# 1_Power.net
KiCad netlist of a schematic drawn in Altium Designer
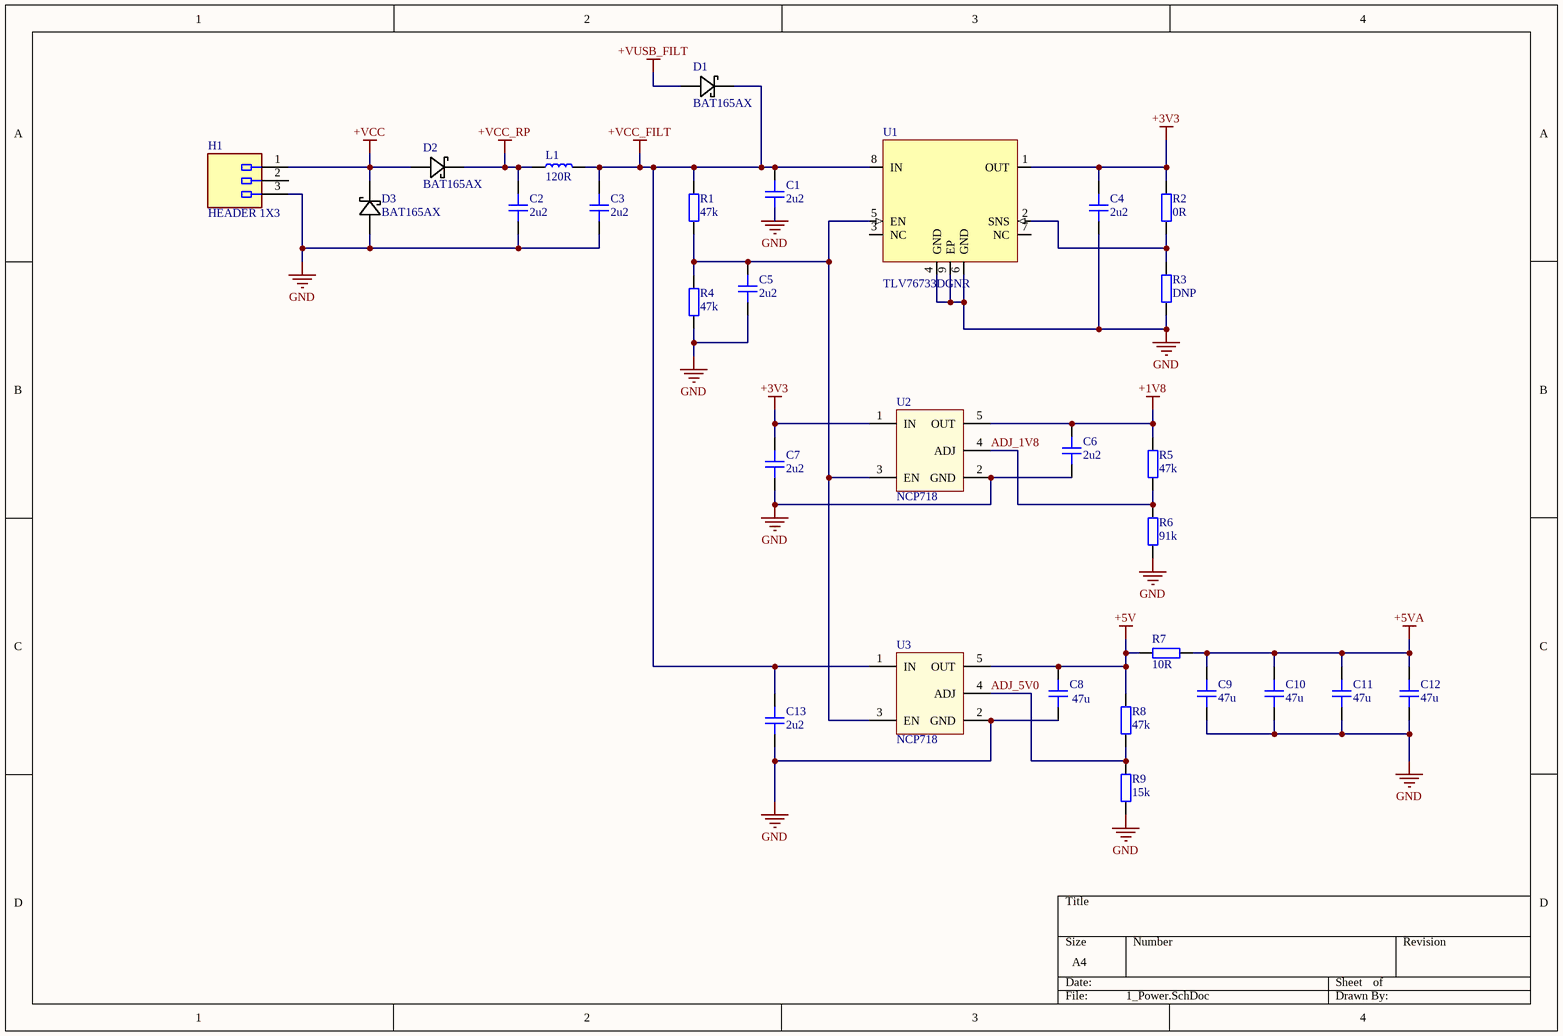
[diagram p0: 1_Power.SchDoc]

(export (version "E")
  (design (tool "Eeschema 10.0.6"))
  (components
    (comp (ref "C1")
      (value "2u2")
      (footprint "CAP_0201")
      (description "Capacitor SMD 0201")
      (libsource (lib "Schematic-Lib-PhilsLab") (part "CAP_0201"))
    )
    (comp (ref "C2")
      (value "2u2")
      (footprint "CAP_0201")
      (description "Capacitor SMD 0201")
      (libsource (lib "Schematic-Lib-PhilsLab") (part "CAP_0201"))
    )
    (comp (ref "C3")
      (value "2u2")
      (footprint "CAP_0201")
      (description "Capacitor SMD 0201")
      (libsource (lib "Schematic-Lib-PhilsLab") (part "CAP_0201"))
    )
    (comp (ref "C4")
      (value "2u2")
      (footprint "CAP_0201")
      (description "Capacitor SMD 0201")
      (libsource (lib "Schematic-Lib-PhilsLab") (part "CAP_0201"))
    )
    (comp (ref "C5")
      (value "2u2")
      (footprint "CAP_0201")
      (description "Capacitor SMD 0201")
      (libsource (lib "Schematic-Lib-PhilsLab") (part "CAP_0201"))
    )
    (comp (ref "C6")
      (value "2u2")
      (footprint "CAP_0201")
      (description "Capacitor SMD 0201")
      (libsource (lib "Schematic-Lib-PhilsLab") (part "CAP_0201"))
    )
    (comp (ref "C7")
      (value "2u2")
      (footprint "CAP_0201")
      (description "Capacitor SMD 0201")
      (libsource (lib "Schematic-Lib-PhilsLab") (part "CAP_0201"))
    )
    (comp (ref "C8")
      (value "47u")
      (footprint "CAP_0201")
      (description "Capacitor SMD 0201")
      (libsource (lib "Schematic-Lib-PhilsLab") (part "CAP_0201"))
    )
    (comp (ref "C9")
      (value "47u")
      (footprint "CAP_0201")
      (description "Capacitor SMD 0201")
      (libsource (lib "Schematic-Lib-PhilsLab") (part "CAP_0201"))
    )
    (comp (ref "C10")
      (value "47u")
      (footprint "CAP_0201")
      (description "Capacitor SMD 0201")
      (libsource (lib "Schematic-Lib-PhilsLab") (part "CAP_0201"))
    )
    (comp (ref "C11")
      (value "47u")
      (footprint "CAP_0201")
      (description "Capacitor SMD 0201")
      (libsource (lib "Schematic-Lib-PhilsLab") (part "CAP_0201"))
    )
    (comp (ref "C12")
      (value "47u")
      (footprint "CAP_0201")
      (description "Capacitor SMD 0201")
      (libsource (lib "Schematic-Lib-PhilsLab") (part "CAP_0201"))
    )
    (comp (ref "C13")
      (value "2u2")
      (footprint "CAP_0201")
      (description "Capacitor SMD 0201")
      (libsource (lib "Schematic-Lib-PhilsLab") (part "CAP_0201"))
    )
    (comp (ref "D1") (value "BAT165AX") (footprint "BAT165AX") (libsource (lib "SCHLib") (part "BAT165AX")))
    (comp (ref "D2") (value "BAT165AX") (footprint "BAT165AX") (libsource (lib "SCHLib") (part "BAT165AX")))
    (comp (ref "D3") (value "BAT165AX") (footprint "BAT165AX") (libsource (lib "SCHLib") (part "BAT165AX")))
    (comp (ref "H1")
      (value "HEADER 1X3")
      (footprint "053048-0310")
      (libsource (lib "SCHLib") (part "053048-0310"))
    )
    (comp (ref "L1")
      (value "120R")
      (footprint "IND_1008")
      (description "Inductor SMD 1008")
      (libsource (lib "Schematic-Lib-PhilsLab") (part "IND_1008"))
    )
    (comp (ref "R1")
      (value "47k")
      (footprint "RES_0402")
      (description "Resistor SMD 0402")
      (libsource (lib "Schematic-Lib-PhilsLab") (part "RES_0402"))
    )
    (comp (ref "R2")
      (value "0R")
      (footprint "RES_0805")
      (description "Resistor SMD 0805")
      (libsource (lib "Schematic-Lib-PhilsLab") (part "RES_0805"))
    )
    (comp (ref "R3")
      (value "DNP")
      (footprint "RES_0805")
      (description "Resistor SMD 0805")
      (libsource (lib "Schematic-Lib-PhilsLab") (part "RES_0805"))
    )
    (comp (ref "R4")
      (value "47k")
      (footprint "RES_0402")
      (description "Resistor SMD 0402")
      (libsource (lib "Schematic-Lib-PhilsLab") (part "RES_0402"))
    )
    (comp (ref "R5")
      (value "47k")
      (footprint "RES_0402")
      (description "Resistor SMD 0402")
      (libsource (lib "Schematic-Lib-PhilsLab") (part "RES_0402"))
    )
    (comp (ref "R6")
      (value "91k")
      (footprint "RES_0402")
      (description "Resistor SMD 0402")
      (libsource (lib "Schematic-Lib-PhilsLab") (part "RES_0402"))
    )
    (comp (ref "R7")
      (value "10R")
      (footprint "RES_0402")
      (description "Resistor SMD 0402")
      (libsource (lib "Schematic-Lib-PhilsLab") (part "RES_0402"))
    )
    (comp (ref "R8")
      (value "47k")
      (footprint "RES_0402")
      (description "Resistor SMD 0402")
      (libsource (lib "Schematic-Lib-PhilsLab") (part "RES_0402"))
    )
    (comp (ref "R9")
      (value "15k")
      (footprint "RES_0402")
      (description "Resistor SMD 0402")
      (libsource (lib "Schematic-Lib-PhilsLab") (part "RES_0402"))
    )
    (comp (ref "U1")
      (value "TLV76733DGNR")
      (footprint "HVSSOP-8")
      (description "1A 3V3 LDO Regulator HVSSOP-8")
      (fields (field (name "MANUFACTURER") "Texas Instruments"))
      (libsource (lib "Schematic-Lib-PhilsLab") (part "TLV76733DGNR"))
    )
    (comp (ref "U2") (value "NCP718") (footprint "NCP718") (libsource (lib "SCHLib") (part "NCP718")))
    (comp (ref "U3") (value "NCP718") (footprint "NCP718") (libsource (lib "SCHLib") (part "NCP718")))
  )
  (nets
    (net (code "1") (name "+1V8") (class "Default")
      (node (ref "C6") (pin "2") (pinfunction "2_2") (pintype "passive"))
      (node (ref "R5") (pin "2") (pinfunction "2_2") (pintype "passive"))
      (node (ref "U2") (pin "5") (pinfunction "OUT_5") (pintype "passive"))
    )
    (net (code "2") (name "+3V3") (class "Default")
      (node (ref "C4") (pin "2") (pinfunction "2_2") (pintype "passive"))
      (node (ref "C7") (pin "2") (pinfunction "2_2") (pintype "passive"))
      (node (ref "R2") (pin "2") (pinfunction "2_2") (pintype "passive"))
      (node (ref "U1") (pin "1") (pinfunction "OUT_1") (pintype "power_in"))
      (node (ref "U2") (pin "1") (pinfunction "IN_1") (pintype "passive"))
    )
    (net (code "3") (name "+5V") (class "Default")
      (node (ref "C8") (pin "2") (pinfunction "2_2") (pintype "passive"))
      (node (ref "R7") (pin "2") (pinfunction "2_2") (pintype "passive"))
      (node (ref "R8") (pin "2") (pinfunction "2_2") (pintype "passive"))
      (node (ref "U3") (pin "5") (pinfunction "OUT_5") (pintype "passive"))
    )
    (net (code "4") (name "+5VA") (class "Default")
      (node (ref "C10") (pin "2") (pinfunction "2_2") (pintype "passive"))
      (node (ref "C11") (pin "2") (pinfunction "2_2") (pintype "passive"))
      (node (ref "C12") (pin "2") (pinfunction "2_2") (pintype "passive"))
      (node (ref "C9") (pin "2") (pinfunction "2_2") (pintype "passive"))
      (node (ref "R7") (pin "1") (pinfunction "1_1") (pintype "passive"))
    )
    (net (code "5") (name "+VCC") (class "Default")
      (node (ref "D2") (pin "2") (pinfunction "2_2") (pintype "passive"))
      (node (ref "D3") (pin "1") (pinfunction "1_1") (pintype "passive"))
      (node (ref "H1") (pin "1") (pinfunction "1_1") (pintype "passive"))
    )
    (net (code "6") (name "+VCC_FILT") (class "Default")
      (node (ref "C1") (pin "2") (pinfunction "2_2") (pintype "passive"))
      (node (ref "C13") (pin "2") (pinfunction "2_2") (pintype "passive"))
      (node (ref "C3") (pin "2") (pinfunction "2_2") (pintype "passive"))
      (node (ref "D1") (pin "1") (pinfunction "1_1") (pintype "passive"))
      (node (ref "L1") (pin "2") (pinfunction "2_2") (pintype "passive"))
      (node (ref "R1") (pin "2") (pinfunction "2_2") (pintype "passive"))
      (node (ref "U1") (pin "8") (pinfunction "IN_8") (pintype "power_in"))
      (node (ref "U3") (pin "1") (pinfunction "IN_1") (pintype "passive"))
    )
    (net (code "7") (name "+VCC_RP") (class "Default")
      (node (ref "C2") (pin "2") (pinfunction "2_2") (pintype "passive"))
      (node (ref "D2") (pin "1") (pinfunction "1_1") (pintype "passive"))
      (node (ref "L1") (pin "1") (pinfunction "1_1") (pintype "passive"))
    )
    (net (code "8") (name "+VUSB_FILT") (class "Default")
      (node (ref "D1") (pin "2") (pinfunction "2_2") (pintype "passive"))
    )
    (net (code "9") (name "/ADJ_1V8") (class "Default")
      (node (ref "R5") (pin "1") (pinfunction "1_1") (pintype "passive"))
      (node (ref "R6") (pin "2") (pinfunction "2_2") (pintype "passive"))
      (node (ref "U2") (pin "4") (pinfunction "ADJ_4") (pintype "passive"))
    )
    (net (code "10") (name "/ADJ_5V0") (class "Default")
      (node (ref "R8") (pin "1") (pinfunction "1_1") (pintype "passive"))
      (node (ref "R9") (pin "2") (pinfunction "2_2") (pintype "passive"))
      (node (ref "U3") (pin "4") (pinfunction "ADJ_4") (pintype "passive"))
    )
    (net (code "11") (name "GND") (class "Default")
      (node (ref "C1") (pin "1") (pinfunction "1_1") (pintype "passive"))
      (node (ref "C10") (pin "1") (pinfunction "1_1") (pintype "passive"))
      (node (ref "C11") (pin "1") (pinfunction "1_1") (pintype "passive"))
      (node (ref "C12") (pin "1") (pinfunction "1_1") (pintype "passive"))
      (node (ref "C13") (pin "1") (pinfunction "1_1") (pintype "passive"))
      (node (ref "C2") (pin "1") (pinfunction "1_1") (pintype "passive"))
      (node (ref "C3") (pin "1") (pinfunction "1_1") (pintype "passive"))
      (node (ref "C4") (pin "1") (pinfunction "1_1") (pintype "passive"))
      (node (ref "C5") (pin "1") (pinfunction "1_1") (pintype "passive"))
      (node (ref "C6") (pin "1") (pinfunction "1_1") (pintype "passive"))
      (node (ref "C7") (pin "1") (pinfunction "1_1") (pintype "passive"))
      (node (ref "C8") (pin "1") (pinfunction "1_1") (pintype "passive"))
      (node (ref "C9") (pin "1") (pinfunction "1_1") (pintype "passive"))
      (node (ref "D3") (pin "2") (pinfunction "2_2") (pintype "passive"))
      (node (ref "H1") (pin "3") (pinfunction "3_3") (pintype "passive"))
      (node (ref "R3") (pin "1") (pinfunction "1_1") (pintype "passive"))
      (node (ref "R4") (pin "1") (pinfunction "1_1") (pintype "passive"))
      (node (ref "R6") (pin "1") (pinfunction "1_1") (pintype "passive"))
      (node (ref "R9") (pin "1") (pinfunction "1_1") (pintype "passive"))
      (node (ref "U1") (pin "4") (pinfunction "GND_4") (pintype "power_in"))
      (node (ref "U1") (pin "6") (pinfunction "GND_6") (pintype "power_in"))
      (node (ref "U1") (pin "9") (pinfunction "EP_9") (pintype "power_in"))
      (node (ref "U2") (pin "2") (pinfunction "GND_2") (pintype "passive"))
      (node (ref "U3") (pin "2") (pinfunction "GND_2") (pintype "passive"))
    )
    (net (code "12") (name "Net-(U1-EN)") (class "Default")
      (node (ref "C5") (pin "2") (pinfunction "2_2") (pintype "passive"))
      (node (ref "R1") (pin "1") (pinfunction "1_1") (pintype "passive"))
      (node (ref "R4") (pin "2") (pinfunction "2_2") (pintype "passive"))
      (node (ref "U1") (pin "5") (pinfunction "EN_5") (pintype "input"))
      (node (ref "U2") (pin "3") (pinfunction "EN_3") (pintype "passive"))
      (node (ref "U3") (pin "3") (pinfunction "EN_3") (pintype "passive"))
    )
    (net (code "13") (name "Net-(U1-SNS)") (class "Default")
      (node (ref "R2") (pin "1") (pinfunction "1_1") (pintype "passive"))
      (node (ref "R3") (pin "2") (pinfunction "2_2") (pintype "passive"))
      (node (ref "U1") (pin "2") (pinfunction "SNS_2") (pintype "input"))
    )
    (net (code "14") (name "unconnected-(H1-Pad2)") (class "Default")
      (node (ref "H1") (pin "2") (pinfunction "2_2") (pintype "passive"))
    )
    (net (code "15") (name "unconnected-(U1-NC-Pad3)") (class "Default")
      (node (ref "U1") (pin "3") (pinfunction "NC_3") (pintype "passive"))
    )
    (net (code "16") (name "unconnected-(U1-NC-Pad7)") (class "Default")
      (node (ref "U1") (pin "7") (pinfunction "NC_7") (pintype "passive"))
    )
  )
)
